# Power.net
KiCad netlist of a schematic drawn in Altium Designer
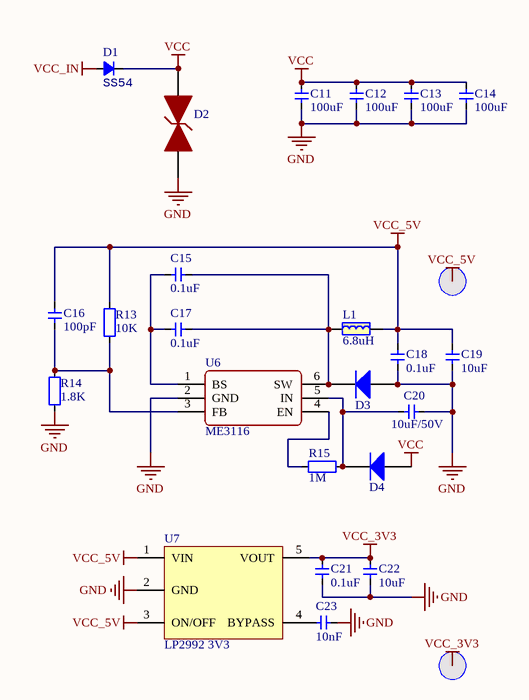
[diagram p0: Power.SchDoc]

(export (version "E")
  (design (tool "Eeschema 10.0.6"))
  (components
    (comp (ref "C11")
      (value "100uF")
      (footprint "1206-CAP")
      (description "Capacitor")
      (libsource (lib "MyPcbLib") (part "电容-1206"))
    )
    (comp (ref "C12")
      (value "100uF")
      (footprint "1206-CAP")
      (description "Capacitor")
      (libsource (lib "MyPcbLib") (part "电容-1206"))
    )
    (comp (ref "C13")
      (value "100uF")
      (footprint "1206-CAP")
      (description "Capacitor")
      (libsource (lib "MyPcbLib") (part "电容-1206"))
    )
    (comp (ref "C14")
      (value "100uF")
      (footprint "1206-CAP")
      (description "Capacitor")
      (libsource (lib "MyPcbLib") (part "电容-1206"))
    )
    (comp (ref "C15")
      (value "0.1uF")
      (footprint "CAP_0402")
      (description "Capacitor")
      (libsource (lib "MyPcbLib") (part "电容-0402"))
    )
    (comp (ref "C16")
      (value "100pF")
      (footprint "CAP_0402")
      (description "Capacitor")
      (libsource (lib "MyPcbLib") (part "电容-0402"))
    )
    (comp (ref "C17")
      (value "0.1uF")
      (footprint "CAP_0402")
      (description "Capacitor")
      (libsource (lib "MyPcbLib") (part "电容-0402"))
    )
    (comp (ref "C18")
      (value "0.1uF")
      (footprint "CAP_0402")
      (description "Capacitor")
      (libsource (lib "MyPcbLib") (part "电容-0402"))
    )
    (comp (ref "C19")
      (value "10uF")
      (footprint "CAP_0402")
      (description "Capacitor")
      (libsource (lib "MyPcbLib") (part "电容-0402"))
    )
    (comp (ref "C20")
      (value "10uF/50V")
      (footprint "CAP_0402")
      (description "Capacitor")
      (libsource (lib "MyPcbLib") (part "电容-0402"))
    )
    (comp (ref "C21")
      (value "0.1uF")
      (footprint "CAP_0402")
      (description "Capacitor")
      (libsource (lib "MyPcbLib") (part "电容-0402"))
    )
    (comp (ref "C22")
      (value "10uF")
      (footprint "CAP_0402")
      (description "Capacitor")
      (libsource (lib "MyPcbLib") (part "电容-0402"))
    )
    (comp (ref "C23")
      (value "10nF")
      (footprint "CAP_0402")
      (description "Capacitor")
      (libsource (lib "MyPcbLib") (part "电容-0402"))
    )
    (comp (ref "D1")
      (value "SS54")
      (footprint "DO-214AC")
      (description "Diode")
      (libsource (lib "KitSprout") (part "Diode_SMA"))
    )
    (comp (ref "D2")
      (value "SMBJ28CA")
      (footprint "SMBJ-CA_MFG")
      (libsource (lib "MyPcbLib") (part "SMBJ28CA"))
    )
    (comp (ref "D3")
      (value "二极管-5819W")
      (footprint "SOD-323")
      (description "40V")
      (libsource (lib "MyPcbLib") (part "二极管-5819W"))
    )
    (comp (ref "D4")
      (value "二极管-5819W")
      (footprint "SOD-323")
      (description "40V")
      (libsource (lib "MyPcbLib") (part "二极管-5819W"))
    )
    (comp (ref "L1") (value "6.8uH") (footprint "IND-201612") (libsource (lib "MyPcbLib") (part "电感-201612")))
    (comp (ref "R13")
      (value "10K")
      (footprint "RES_0402")
      (description "Resistor")
      (libsource (lib "MyPcbLib") (part "电阻-0402"))
    )
    (comp (ref "R14")
      (value "1.8K")
      (footprint "RES_0402")
      (description "Resistor")
      (libsource (lib "MyPcbLib") (part "电阻-0402"))
    )
    (comp (ref "R15")
      (value "1M")
      (footprint "RES_0402")
      (description "Resistor")
      (libsource (lib "") (part "电阻-0402_1"))
    )
    (comp (ref "T1") (value "测试点") (footprint "TEST_PT") (libsource (lib "MyPcbLib") (part "测试点")))
    (comp (ref "T2") (value "测试点") (footprint "TEST_PT") (libsource (lib "MyPcbLib") (part "测试点")))
    (comp (ref "U6")
      (value "ME3116")
      (footprint "SOT23-6")
      (description "DC-DC")
      (libsource (lib "MyPcbLib") (part "ME3116"))
    )
    (comp (ref "U7")
      (value "LP2992 3V3")
      (footprint "SOT23-5")
      (description "LDO")
      (libsource (lib "MyPcbLib") (part "LP2992"))
    )
  )
  (nets
    (net (code "1") (name "GND") (class "Default")
      (node (ref "C11") (pin "1") (pinfunction "1_1") (pintype "passive"))
      (node (ref "C12") (pin "1") (pinfunction "1_1") (pintype "passive"))
      (node (ref "C13") (pin "1") (pinfunction "1_1") (pintype "passive"))
      (node (ref "C14") (pin "1") (pinfunction "1_1") (pintype "passive"))
      (node (ref "C18") (pin "1") (pinfunction "1_1") (pintype "passive"))
      (node (ref "C19") (pin "1") (pinfunction "1_1") (pintype "passive"))
      (node (ref "C20") (pin "1") (pinfunction "1_1") (pintype "passive"))
      (node (ref "C21") (pin "1") (pinfunction "1_1") (pintype "passive"))
      (node (ref "C22") (pin "1") (pinfunction "1_1") (pintype "passive"))
      (node (ref "C23") (pin "1") (pinfunction "1_1") (pintype "passive"))
      (node (ref "D2") (pin "1") (pinfunction "1_1") (pintype "passive"))
      (node (ref "D3") (pin "1") (pinfunction "A_1") (pintype "passive"))
      (node (ref "R14") (pin "1") (pinfunction "1_1") (pintype "passive"))
      (node (ref "U6") (pin "2") (pinfunction "GND_2") (pintype "passive"))
      (node (ref "U7") (pin "2") (pinfunction "GND_2") (pintype "passive"))
    )
    (net (code "2") (name "Net-(D3-K)") (class "Default")
      (node (ref "C15") (pin "1") (pinfunction "1_1") (pintype "passive"))
      (node (ref "C17") (pin "1") (pinfunction "1_1") (pintype "passive"))
      (node (ref "D3") (pin "2") (pinfunction "K_2") (pintype "passive"))
      (node (ref "L1") (pin "1") (pintype "passive"))
      (node (ref "U6") (pin "6") (pinfunction "SW_6") (pintype "passive"))
    )
    (net (code "3") (name "Net-(D4-K)") (class "Default")
      (node (ref "C20") (pin "2") (pinfunction "2_2") (pintype "passive"))
      (node (ref "D4") (pin "2") (pinfunction "K_2") (pintype "passive"))
      (node (ref "R15") (pin "1") (pinfunction "1_1") (pintype "passive"))
      (node (ref "U6") (pin "5") (pinfunction "IN_5") (pintype "passive"))
    )
    (net (code "4") (name "Net-(U6-BS)") (class "Default")
      (node (ref "C15") (pin "2") (pinfunction "2_2") (pintype "passive"))
      (node (ref "C17") (pin "2") (pinfunction "2_2") (pintype "passive"))
      (node (ref "U6") (pin "1") (pinfunction "BS_1") (pintype "passive"))
    )
    (net (code "5") (name "Net-(U6-EN)") (class "Default")
      (node (ref "R15") (pin "2") (pinfunction "2_2") (pintype "passive"))
      (node (ref "U6") (pin "4") (pinfunction "EN_4") (pintype "passive"))
    )
    (net (code "6") (name "Net-(U6-FB)") (class "Default")
      (node (ref "C16") (pin "2") (pinfunction "2_2") (pintype "passive"))
      (node (ref "R13") (pin "1") (pinfunction "1_1") (pintype "passive"))
      (node (ref "R14") (pin "2") (pinfunction "2_2") (pintype "passive"))
      (node (ref "U6") (pin "3") (pinfunction "FB_3") (pintype "passive"))
    )
    (net (code "7") (name "Net-(U7-BYPASS)") (class "Default")
      (node (ref "C23") (pin "2") (pinfunction "2_2") (pintype "passive"))
      (node (ref "U7") (pin "4") (pinfunction "BYPASS_4") (pintype "passive"))
    )
    (net (code "8") (name "VCC") (class "Default")
      (node (ref "C11") (pin "2") (pinfunction "2_2") (pintype "passive"))
      (node (ref "C12") (pin "2") (pinfunction "2_2") (pintype "passive"))
      (node (ref "C13") (pin "2") (pinfunction "2_2") (pintype "passive"))
      (node (ref "C14") (pin "2") (pinfunction "2_2") (pintype "passive"))
      (node (ref "D1") (pin "2") (pinfunction "K_2") (pintype "passive"))
      (node (ref "D2") (pin "2") (pinfunction "2_2") (pintype "passive"))
      (node (ref "D4") (pin "1") (pinfunction "A_1") (pintype "passive"))
    )
    (net (code "9") (name "VCC_3V3") (class "Default")
      (node (ref "C21") (pin "2") (pinfunction "2_2") (pintype "passive"))
      (node (ref "C22") (pin "2") (pinfunction "2_2") (pintype "passive"))
      (node (ref "T2") (pin "0") (pinfunction "0_0") (pintype "passive"))
      (node (ref "U7") (pin "5") (pinfunction "VOUT_5") (pintype "passive"))
    )
    (net (code "10") (name "VCC_5V") (class "Default")
      (node (ref "C16") (pin "1") (pinfunction "1_1") (pintype "passive"))
      (node (ref "C18") (pin "2") (pinfunction "2_2") (pintype "passive"))
      (node (ref "C19") (pin "2") (pinfunction "2_2") (pintype "passive"))
      (node (ref "L1") (pin "2") (pinfunction "2_2") (pintype "passive"))
      (node (ref "R13") (pin "2") (pinfunction "2_2") (pintype "passive"))
      (node (ref "T1") (pin "0") (pinfunction "0_0") (pintype "passive"))
      (node (ref "U7") (pin "1") (pinfunction "VIN_1") (pintype "passive"))
      (node (ref "U7") (pin "3") (pinfunction "ON/OFF_3") (pintype "passive"))
    )
    (net (code "11") (name "VCC_IN") (class "Default")
      (node (ref "D1") (pin "1") (pinfunction "A_1") (pintype "passive"))
    )
  )
)
